# SCH_Carga2BM_2023-11-16.net
KiCad netlist of a schematic drawn in EasyEDA
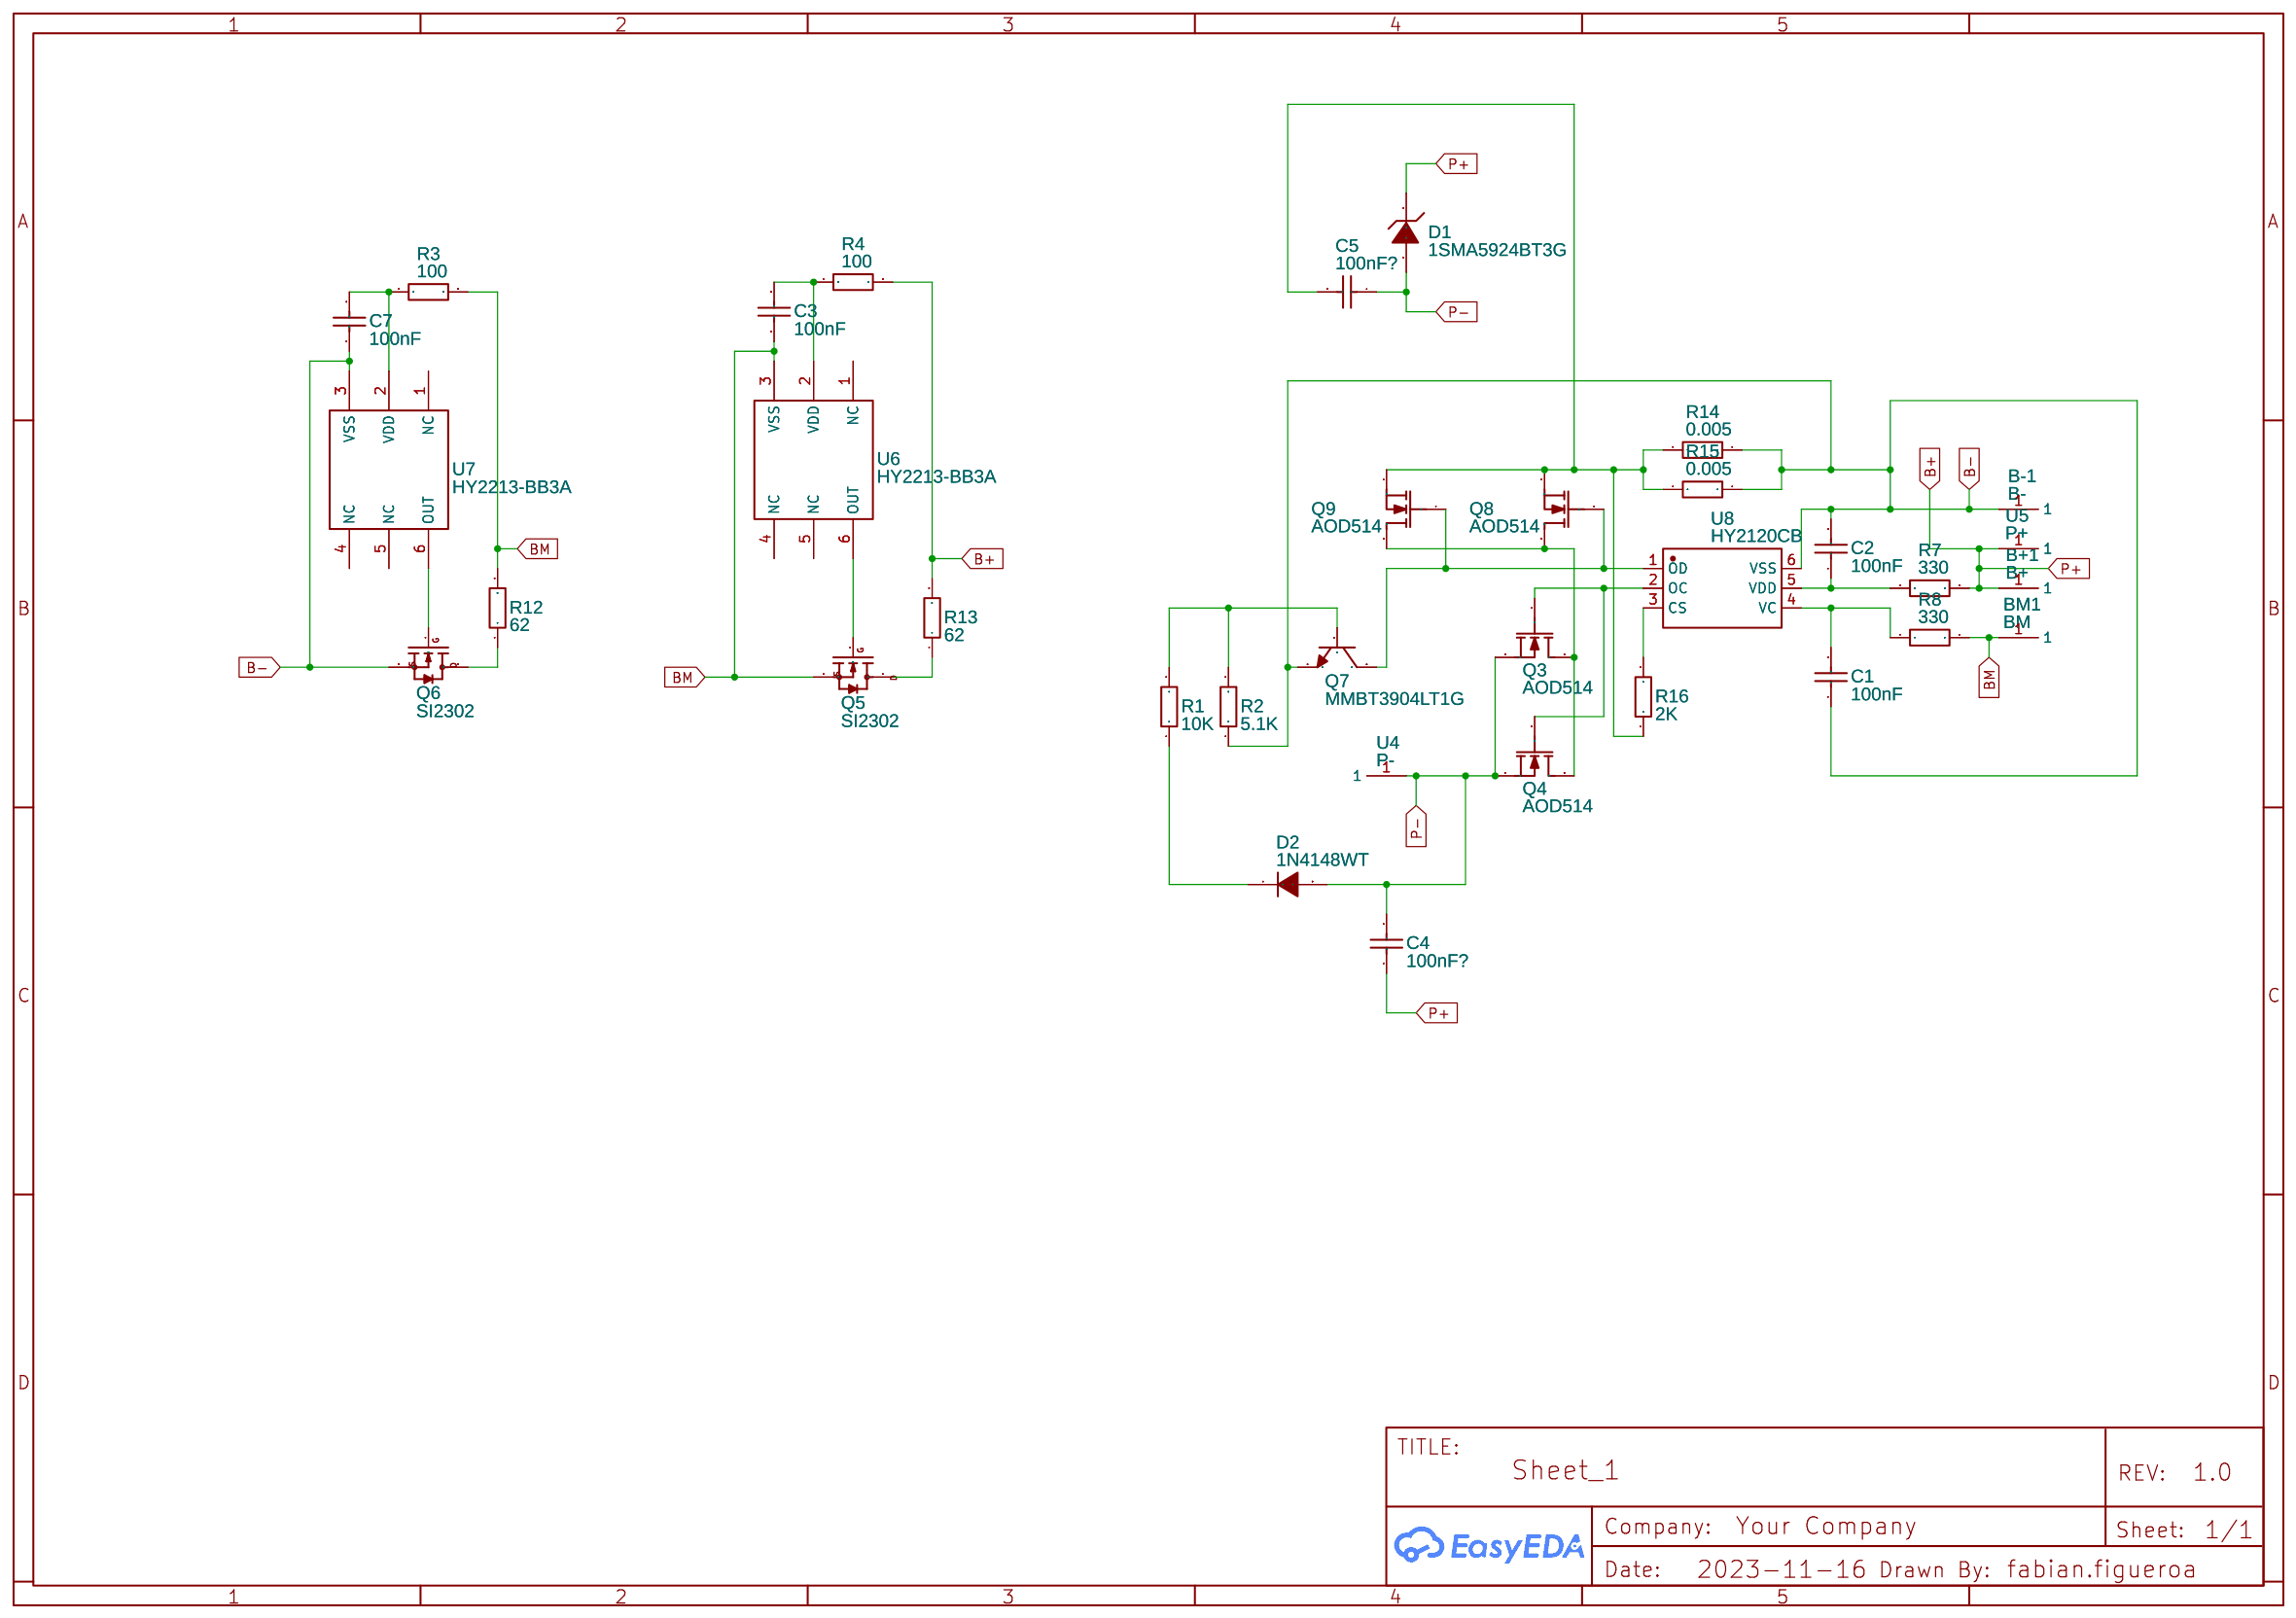
[diagram p0: schematic sheet]

(export (version "E")
  (design (tool "Eeschema 10.0.6"))
  (components
    (comp (ref "B+1")
      (value "B+")
      (fields (field (name "Manufacturer Part") "?"))
      (libsource (lib "") (part "Unknown_1005_-515"))
    )
    (comp (ref "B-1")
      (value "B-")
      (fields (field (name "Manufacturer Part") "?"))
      (libsource (lib "") (part "Unknown_1005_-555"))
    )
    (comp (ref "BM1")
      (value "BM")
      (fields (field (name "Manufacturer Part") "?"))
      (libsource (lib "") (part "Unknown_1005_-490"))
    )
    (comp (ref "C1")
      (value "100nF")
      (fields (field (name "Manufacturer Part") "CL10B104JB8NNNC") (field (name "Manufacturer") "SAMSUNG"))
      (libsource (lib "") (part "CL10B104JB8NNNC"))
    )
    (comp (ref "C2")
      (value "100nF")
      (fields (field (name "Manufacturer Part") "CL10B104JB8NNNC") (field (name "Manufacturer") "SAMSUNG"))
      (libsource (lib "") (part "CL10B104JB8NNNC"))
    )
    (comp (ref "C3")
      (value "100nF")
      (fields (field (name "Manufacturer Part") "CL10B104JB8NNNC") (field (name "Manufacturer") "SAMSUNG"))
      (libsource (lib "") (part "CL10B104JB8NNNC"))
    )
    (comp (ref "C4")
      (value "100nF?")
      (fields (field (name "Manufacturer Part") "CL10B104JB8NNNC") (field (name "Manufacturer") "SAMSUNG"))
      (libsource (lib "") (part "CL10B104JB8NNNC"))
    )
    (comp (ref "C5")
      (value "100nF?")
      (fields (field (name "Manufacturer Part") "CL10B104JB8NNNC") (field (name "Manufacturer") "SAMSUNG"))
      (libsource (lib "") (part "CL10B104JB8NNNC_1"))
    )
    (comp (ref "C7")
      (value "100nF")
      (fields (field (name "Manufacturer Part") "CL10B104JB8NNNC") (field (name "Manufacturer") "SAMSUNG"))
      (libsource (lib "") (part "CL10B104JB8NNNC"))
    )
    (comp (ref "D1")
      (value "1SMA5924BT3G")
      (fields (field (name "Manufacturer") "ON"))
      (libsource (lib "") (part "Unknown_705_-695"))
    )
    (comp (ref "D2")
      (value "1N4148WT")
      (fields (field (name "Manufacturer") "CJ"))
      (libsource (lib "") (part "Unknown_645_-365"))
    )
    (comp (ref "Q3")
      (value "AOD514")
      (fields (field (name "Manufacturer") "Alpha & Omega Semicon"))
      (libsource (lib "") (part "Unknown_770_-490"))
    )
    (comp (ref "Q4")
      (value "AOD514")
      (fields (field (name "Manufacturer") "Alpha & Omega Semicon"))
      (libsource (lib "") (part "Unknown_770_-430"))
    )
    (comp (ref "Q5")
      (value "SI2302")
      (fields (field (name "Manufacturer") "Hottech"))
      (libsource (lib "") (part "Unknown_425_-480"))
    )
    (comp (ref "Q6")
      (value "SI2302")
      (fields (field (name "Manufacturer") "Hottech"))
      (libsource (lib "") (part "Unknown_210_-485"))
    )
    (comp (ref "Q7")
      (value "MMBT3904LT1G")
      (fields (field (name "Manufacturer") "ON"))
      (libsource (lib "") (part "Unknown_670_-485"))
    )
    (comp (ref "Q8")
      (value "AOD514")
      (fields (field (name "Manufacturer") "Alpha & Omega Semicon"))
      (libsource (lib "") (part "Unknown_785_-555"))
    )
    (comp (ref "Q9")
      (value "AOD514")
      (fields (field (name "Manufacturer") "Alpha & Omega Semicon"))
      (libsource (lib "") (part "Unknown_705_-555"))
    )
    (comp (ref "R1")
      (value "10K")
      (fields (field (name "Manufacturer Part") "RMC16K103FTP") (field (name "Manufacturer") "KAMAYA"))
      (libsource (lib "") (part "RMC16K103FTP"))
    )
    (comp (ref "R2")
      (value "5.1K")
      (fields (field (name "Manufacturer Part") "0603WAF5101T5E") (field (name "Manufacturer") "UniOhm"))
      (libsource (lib "") (part "0603WAF5101T5E"))
    )
    (comp (ref "R3")
      (value "100")
      (fields (field (name "Manufacturer Part") "RTT031000FTP") (field (name "Manufacturer") "RALEC"))
      (libsource (lib "") (part "RTT031000FTP"))
    )
    (comp (ref "R4")
      (value "100")
      (fields (field (name "Manufacturer Part") "RTT031000FTP") (field (name "Manufacturer") "RALEC"))
      (libsource (lib "") (part "RTT031000FTP"))
    )
    (comp (ref "R7")
      (value "330")
      (fields (field (name "Manufacturer Part") "0603WAF3300T5E") (field (name "Manufacturer") "UniOhm"))
      (libsource (lib "") (part "0603WAF3300T5E"))
    )
    (comp (ref "R8")
      (value "330")
      (fields (field (name "Manufacturer Part") "0603WAF3300T5E") (field (name "Manufacturer") "UniOhm"))
      (libsource (lib "") (part "0603WAF3300T5E"))
    )
    (comp (ref "R12")
      (value "62")
      (fields (field (name "Manufacturer Part") "CR2512J62RE04") (field (name "Manufacturer") "EVER OHMS"))
      (libsource (lib "") (part "CR2512J62RE04"))
    )
    (comp (ref "R13")
      (value "62")
      (fields (field (name "Manufacturer Part") "CR2512J62RE04") (field (name "Manufacturer") "EVER OHMS"))
      (libsource (lib "") (part "CR2512J62RE04"))
    )
    (comp (ref "R14")
      (value "0.005")
      (fields (field (name "Manufacturer Part") "CUM2512-24FR005") (field (name "Manufacturer") "FORT"))
      (libsource (lib "") (part "CUM2512-24FR005"))
    )
    (comp (ref "R15")
      (value "0.005")
      (fields (field (name "Manufacturer Part") "CUM2512-24FR005") (field (name "Manufacturer") "FORT"))
      (libsource (lib "") (part "CUM2512-24FR005"))
    )
    (comp (ref "R16")
      (value "2K")
      (fields (field (name "Manufacturer Part") "RC0603FR-072KL") (field (name "Manufacturer") "YAGEO"))
      (libsource (lib "") (part "RC0603FR-072KL"))
    )
    (comp (ref "U4")
      (value "P-")
      (fields (field (name "Manufacturer Part") "?"))
      (libsource (lib "") (part "Unknown_705_-420"))
    )
    (comp (ref "U5")
      (value "P+")
      (fields (field (name "Manufacturer Part") "?"))
      (libsource (lib "") (part "Unknown_1005_-535"))
    )
    (comp (ref "U6")
      (value "HY2213-BB3A")
      (fields (field (name "Manufacturer") "HYCON"))
      (libsource (lib "") (part "Unknown_405_-580"))
    )
    (comp (ref "U7")
      (value "HY2213-BB3A")
      (fields (field (name "Manufacturer") "HYCON"))
      (libsource (lib "") (part "Unknown_190_-575"))
    )
    (comp (ref "U8")
      (value "HY2120CB")
      (fields (field (name "Manufacturer") "HYCON"))
      (libsource (lib "") (part "Unknown_865_-515"))
    )
  )
  (nets
    (net (code "1") (name "B+") (class "Default")
      (node (ref "B+1") (pin "1") (pinfunction "1_1") (pintype "unspecified"))
      (node (ref "C4") (pin "1") (pinfunction "1_1") (pintype "input"))
      (node (ref "D1") (pin "2") (pinfunction "K_2") (pintype "unspecified"))
      (node (ref "R13") (pin "2") (pinfunction "2_2") (pintype "unspecified"))
      (node (ref "R4") (pin "2") (pinfunction "2_2") (pintype "input"))
      (node (ref "R7") (pin "2") (pinfunction "2_2") (pintype "input"))
      (node (ref "U5") (pin "1") (pinfunction "1_1") (pintype "unspecified"))
    )
    (net (code "2") (name "B-") (class "Default")
      (node (ref "B-1") (pin "1") (pinfunction "1_1") (pintype "unspecified"))
      (node (ref "C1") (pin "1") (pinfunction "1_1") (pintype "input"))
      (node (ref "C2") (pin "2") (pinfunction "2_2") (pintype "input"))
      (node (ref "C7") (pin "1") (pinfunction "1_1") (pintype "input"))
      (node (ref "Q6") (pin "2") (pinfunction "S_2") (pintype "unspecified"))
      (node (ref "Q7") (pin "2") (pinfunction "2_2") (pintype "input"))
      (node (ref "R14") (pin "1") (pinfunction "1_1") (pintype "unspecified"))
      (node (ref "R15") (pin "1") (pinfunction "1_1") (pintype "unspecified"))
      (node (ref "R2") (pin "1") (pinfunction "1_1") (pintype "input"))
      (node (ref "U7") (pin "3") (pinfunction "VSS_3") (pintype "unspecified"))
      (node (ref "U8") (pin "6") (pinfunction "VSS_6") (pintype "unspecified"))
    )
    (net (code "3") (name "BM") (class "Default")
      (node (ref "BM1") (pin "1") (pinfunction "1_1") (pintype "unspecified"))
      (node (ref "C3") (pin "1") (pinfunction "1_1") (pintype "input"))
      (node (ref "Q5") (pin "2") (pinfunction "S_2") (pintype "unspecified"))
      (node (ref "R12") (pin "2") (pinfunction "2_2") (pintype "unspecified"))
      (node (ref "R3") (pin "2") (pinfunction "2_2") (pintype "input"))
      (node (ref "R8") (pin "2") (pinfunction "2_2") (pintype "input"))
      (node (ref "U6") (pin "3") (pinfunction "VSS_3") (pintype "unspecified"))
    )
    (net (code "4") (name "Net-(D2-K)") (class "Default")
      (node (ref "D2") (pin "1") (pinfunction "K_1") (pintype "unspecified"))
      (node (ref "R1") (pin "1") (pinfunction "1_1") (pintype "unspecified"))
    )
    (net (code "5") (name "Net-(Q3-D)") (class "Default")
      (node (ref "Q3") (pin "3") (pinfunction "D_3") (pintype "unspecified"))
      (node (ref "Q4") (pin "3") (pinfunction "D_3") (pintype "unspecified"))
      (node (ref "Q8") (pin "3") (pinfunction "D_3") (pintype "unspecified"))
      (node (ref "Q9") (pin "3") (pinfunction "D_3") (pintype "unspecified"))
    )
    (net (code "6") (name "Net-(Q3-G)") (class "Default")
      (node (ref "Q3") (pin "1") (pinfunction "G_1") (pintype "unspecified"))
      (node (ref "Q4") (pin "1") (pinfunction "G_1") (pintype "unspecified"))
      (node (ref "U8") (pin "2") (pinfunction "OC_2") (pintype "unspecified"))
    )
    (net (code "7") (name "Net-(Q5-D)") (class "Default")
      (node (ref "Q5") (pin "3") (pinfunction "D_3") (pintype "unspecified"))
      (node (ref "R13") (pin "1") (pinfunction "1_1") (pintype "unspecified"))
    )
    (net (code "8") (name "Net-(Q5-G)") (class "Default")
      (node (ref "Q5") (pin "1") (pinfunction "G_1") (pintype "unspecified"))
      (node (ref "U6") (pin "6") (pinfunction "OUT_6") (pintype "unspecified"))
    )
    (net (code "9") (name "Net-(Q6-D)") (class "Default")
      (node (ref "Q6") (pin "3") (pinfunction "D_3") (pintype "unspecified"))
      (node (ref "R12") (pin "1") (pinfunction "1_1") (pintype "unspecified"))
    )
    (net (code "10") (name "Net-(Q6-G)") (class "Default")
      (node (ref "Q6") (pin "1") (pinfunction "G_1") (pintype "unspecified"))
      (node (ref "U7") (pin "6") (pinfunction "OUT_6") (pintype "unspecified"))
    )
    (net (code "11") (name "Net-(Q7-Pad1)") (class "Default")
      (node (ref "Q7") (pin "1") (pinfunction "1_1") (pintype "input"))
      (node (ref "R1") (pin "2") (pinfunction "2_2") (pintype "unspecified"))
      (node (ref "R2") (pin "2") (pinfunction "2_2") (pintype "input"))
    )
    (net (code "12") (name "Net-(Q8-G)") (class "Default")
      (node (ref "Q7") (pin "3") (pinfunction "3_3") (pintype "input"))
      (node (ref "Q8") (pin "1") (pinfunction "G_1") (pintype "unspecified"))
      (node (ref "Q9") (pin "1") (pinfunction "G_1") (pintype "unspecified"))
      (node (ref "U8") (pin "1") (pinfunction "OD_1") (pintype "unspecified"))
    )
    (net (code "13") (name "Net-(Q8-S)") (class "Default")
      (node (ref "C5") (pin "2") (pinfunction "2_2") (pintype "input"))
      (node (ref "Q8") (pin "2") (pinfunction "S_2") (pintype "unspecified"))
      (node (ref "Q9") (pin "2") (pinfunction "S_2") (pintype "unspecified"))
      (node (ref "R14") (pin "2") (pinfunction "2_2") (pintype "unspecified"))
      (node (ref "R15") (pin "2") (pinfunction "2_2") (pintype "unspecified"))
      (node (ref "R16") (pin "1") (pinfunction "1_1") (pintype "input"))
    )
    (net (code "14") (name "Net-(U6-VDD)") (class "Default")
      (node (ref "C3") (pin "2") (pinfunction "2_2") (pintype "input"))
      (node (ref "R4") (pin "1") (pinfunction "1_1") (pintype "input"))
      (node (ref "U6") (pin "2") (pinfunction "VDD_2") (pintype "unspecified"))
    )
    (net (code "15") (name "Net-(U7-VDD)") (class "Default")
      (node (ref "C7") (pin "2") (pinfunction "2_2") (pintype "input"))
      (node (ref "R3") (pin "1") (pinfunction "1_1") (pintype "input"))
      (node (ref "U7") (pin "2") (pinfunction "VDD_2") (pintype "unspecified"))
    )
    (net (code "16") (name "Net-(U8-CS)") (class "Default")
      (node (ref "R16") (pin "2") (pinfunction "2_2") (pintype "input"))
      (node (ref "U8") (pin "3") (pinfunction "CS_3") (pintype "unspecified"))
    )
    (net (code "17") (name "Net-(U8-VC)") (class "Default")
      (node (ref "C1") (pin "2") (pinfunction "2_2") (pintype "input"))
      (node (ref "R8") (pin "1") (pinfunction "1_1") (pintype "input"))
      (node (ref "U8") (pin "4") (pinfunction "VC_4") (pintype "unspecified"))
    )
    (net (code "18") (name "Net-(U8-VDD)") (class "Default")
      (node (ref "C2") (pin "1") (pinfunction "1_1") (pintype "input"))
      (node (ref "R7") (pin "1") (pinfunction "1_1") (pintype "input"))
      (node (ref "U8") (pin "5") (pinfunction "VDD_5") (pintype "unspecified"))
    )
    (net (code "19") (name "P-") (class "Default")
      (node (ref "C4") (pin "2") (pinfunction "2_2") (pintype "input"))
      (node (ref "C5") (pin "1") (pinfunction "1_1") (pintype "input"))
      (node (ref "D1") (pin "1") (pinfunction "A_1") (pintype "unspecified"))
      (node (ref "D2") (pin "2") (pinfunction "A_2") (pintype "unspecified"))
      (node (ref "Q3") (pin "2") (pinfunction "S_2") (pintype "unspecified"))
      (node (ref "Q4") (pin "2") (pinfunction "S_2") (pintype "unspecified"))
      (node (ref "U4") (pin "1") (pinfunction "1_1") (pintype "unspecified"))
    )
    (net (code "20") (name "unconnected-(U6-NC-Pad1)") (class "Default")
      (node (ref "U6") (pin "1") (pinfunction "NC_1") (pintype "unspecified"))
    )
    (net (code "21") (name "unconnected-(U6-NC-Pad4)") (class "Default")
      (node (ref "U6") (pin "4") (pinfunction "NC_4") (pintype "unspecified"))
    )
    (net (code "22") (name "unconnected-(U6-NC-Pad5)") (class "Default")
      (node (ref "U6") (pin "5") (pinfunction "NC_5") (pintype "unspecified"))
    )
    (net (code "23") (name "unconnected-(U7-NC-Pad1)") (class "Default")
      (node (ref "U7") (pin "1") (pinfunction "NC_1") (pintype "unspecified"))
    )
    (net (code "24") (name "unconnected-(U7-NC-Pad4)") (class "Default")
      (node (ref "U7") (pin "4") (pinfunction "NC_4") (pintype "unspecified"))
    )
    (net (code "25") (name "unconnected-(U7-NC-Pad5)") (class "Default")
      (node (ref "U7") (pin "5") (pinfunction "NC_5") (pintype "unspecified"))
    )
  )
)
